# 2.net
KiCad netlist of a schematic drawn in EAGLE
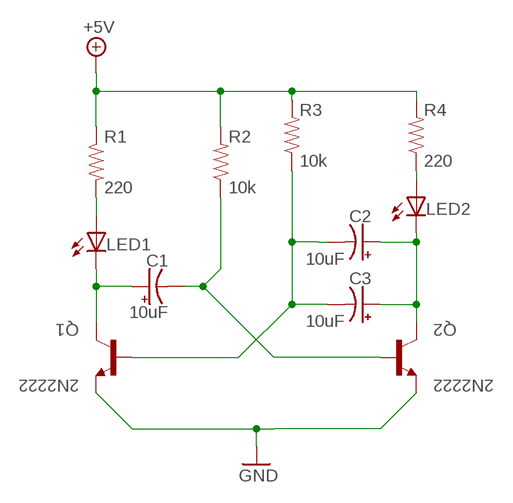
[diagram p0: schematic, sheet 1]

(export (version "E")
  (design (tool "Eeschema 10.0.6"))
  (components
    (comp (ref "C1")
      (value "10uF")
      (footprint "eagle-import:CPOL-RADIAL-2.5MM-5MM")
      (libsource (lib "eagle-import") (part "10UF-POLAR-RADIAL-2.5MM-25V-20%"))
    )
    (comp (ref "C2")
      (value "10uF")
      (footprint "eagle-import:CPOL-RADIAL-2.5MM-5MM")
      (libsource (lib "eagle-import") (part "10UF-POLAR-RADIAL-2.5MM-25V-20%"))
    )
    (comp (ref "C3")
      (value "10uF")
      (footprint "eagle-import:CPOL-RADIAL-2.5MM-5MM")
      (libsource (lib "eagle-import") (part "10UF-POLAR-RADIAL-2.5MM-25V-20%"))
    )
    (comp (ref "LED1")
      (value "LED5MM")
      (footprint "eagle-import:LED5MM")
      (libsource (lib "eagle-import") (part "LED5MM"))
    )
    (comp (ref "LED2")
      (value "LED5MM")
      (footprint "eagle-import:LED5MM")
      (libsource (lib "eagle-import") (part "LED5MM"))
    )
    (comp (ref "Q1")
      (value "2N2222")
      (footprint "eagle-import:TO92-EBC-OVAL")
      (libsource (lib "eagle-import") (part "2N2222"))
    )
    (comp (ref "Q2")
      (value "2N2222")
      (footprint "eagle-import:TO92-EBC-OVAL")
      (libsource (lib "eagle-import") (part "2N2222"))
    )
    (comp (ref "R1")
      (value "220")
      (footprint "eagle-import:AXIAL-0.3")
      (libsource (lib "eagle-import") (part "100OHM-HORIZ-1/4W-1%"))
    )
    (comp (ref "R2")
      (value "10k")
      (footprint "eagle-import:AXIAL-0.3")
      (libsource (lib "eagle-import") (part "100OHM-HORIZ-1/4W-1%"))
    )
    (comp (ref "R3")
      (value "10k")
      (footprint "eagle-import:AXIAL-0.3")
      (libsource (lib "eagle-import") (part "100OHM-HORIZ-1/4W-1%"))
    )
    (comp (ref "R4")
      (value "220")
      (footprint "eagle-import:AXIAL-0.3")
      (libsource (lib "eagle-import") (part "100OHM-HORIZ-1/4W-1%"))
    )
  )
  (nets
    (net (code "1") (name "+5V") (class "Default")
      (node (ref "R1") (pin "P$1") (pinfunction "1_P$1") (pintype "passive"))
      (node (ref "R2") (pin "P$2") (pinfunction "2_P$2") (pintype "passive"))
      (node (ref "R3") (pin "P$2") (pinfunction "2_P$2") (pintype "passive"))
      (node (ref "R4") (pin "P$2") (pinfunction "2_P$2") (pintype "passive"))
    )
    (net (code "2") (name "GND") (class "Default")
      (node (ref "Q1") (pin "E") (pinfunction "E_E") (pintype "passive"))
      (node (ref "Q2") (pin "E") (pinfunction "E_E") (pintype "passive"))
    )
    (net (code "3") (name "Net-(C1-+)") (class "Default")
      (node (ref "C1") (pin "1") (pinfunction "+_1") (pintype "passive"))
      (node (ref "LED1") (pin "K") (pinfunction "C_K") (pintype "passive"))
      (node (ref "Q1") (pin "C") (pinfunction "C_C") (pintype "passive"))
    )
    (net (code "4") (name "Net-(C1--)") (class "Default")
      (node (ref "C1") (pin "2") (pinfunction "-_2") (pintype "passive"))
      (node (ref "Q2") (pin "B") (pinfunction "B_B") (pintype "passive"))
      (node (ref "R2") (pin "P$1") (pinfunction "1_P$1") (pintype "passive"))
    )
    (net (code "5") (name "Net-(C2-+)") (class "Default")
      (node (ref "C2") (pin "1") (pinfunction "+_1") (pintype "passive"))
      (node (ref "C3") (pin "1") (pinfunction "+_1") (pintype "passive"))
      (node (ref "LED2") (pin "K") (pinfunction "C_K") (pintype "passive"))
      (node (ref "Q2") (pin "C") (pinfunction "C_C") (pintype "passive"))
    )
    (net (code "6") (name "Net-(C2--)") (class "Default")
      (node (ref "C2") (pin "2") (pinfunction "-_2") (pintype "passive"))
      (node (ref "C3") (pin "2") (pinfunction "-_2") (pintype "passive"))
      (node (ref "Q1") (pin "B") (pinfunction "B_B") (pintype "passive"))
      (node (ref "R3") (pin "P$1") (pinfunction "1_P$1") (pintype "passive"))
    )
    (net (code "7") (name "Net-(R1-2)") (class "Default")
      (node (ref "LED1") (pin "A") (pinfunction "A_A") (pintype "passive"))
      (node (ref "R1") (pin "P$2") (pinfunction "2_P$2") (pintype "passive"))
    )
    (net (code "8") (name "Net-(R4-1)") (class "Default")
      (node (ref "LED2") (pin "A") (pinfunction "A_A") (pintype "passive"))
      (node (ref "R4") (pin "P$1") (pinfunction "1_P$1") (pintype "passive"))
    )
  )
)
